# torque.net
KiCad netlist of a schematic drawn in EAGLE
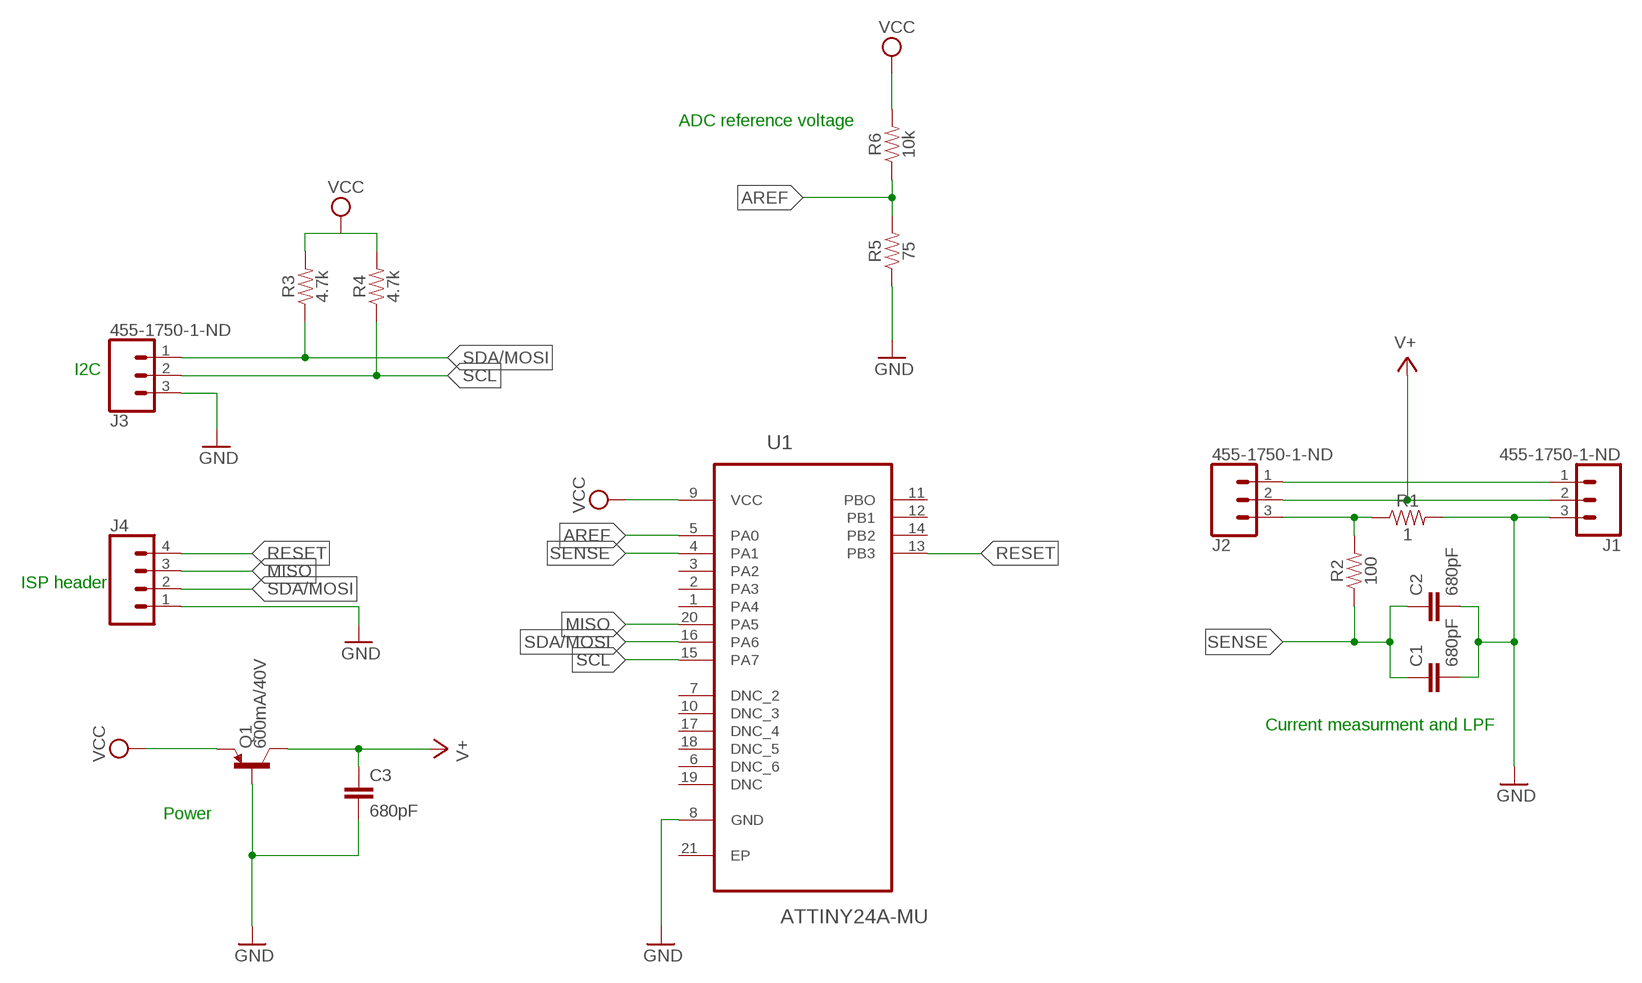
[diagram p0: schematic, sheet 1]

(export (version "E")
  (design (tool "Eeschema 10.0.6"))
  (components
    (comp (ref "C1")
      (value "680pF")
      (footprint "eagle-import:0603")
      (libsource (lib "eagle-import") (part "680PF-0603-50V-10%"))
    )
    (comp (ref "C2")
      (value "680pF")
      (footprint "eagle-import:0603")
      (libsource (lib "eagle-import") (part "680PF-0603-50V-10%"))
    )
    (comp (ref "C3")
      (value "680pF")
      (footprint "eagle-import:0603")
      (libsource (lib "eagle-import") (part "680PF-0603-50V-10%"))
    )
    (comp (ref "J1")
      (value "455-1750-1-ND")
      (footprint "eagle-import:1X03")
      (libsource (lib "eagle-import") (part "CONN_03"))
    )
    (comp (ref "J2")
      (value "455-1750-1-ND")
      (footprint "eagle-import:1X03")
      (libsource (lib "eagle-import") (part "CONN_03"))
    )
    (comp (ref "J3")
      (value "455-1750-1-ND")
      (footprint "eagle-import:1X03")
      (libsource (lib "eagle-import") (part "CONN_03"))
    )
    (comp (ref "J4")
      (value "CONN_04SMD_RA_FEMALE")
      (footprint "eagle-import:1X04_SMD_RA_FEMALE")
      (libsource (lib "eagle-import") (part "CONN_04SMD_RA_FEMALE"))
    )
    (comp (ref "Q1")
      (value "600mA/40V")
      (footprint "eagle-import:SOT23-3")
      (libsource (lib "eagle-import") (part "TRANS_PNP-MMBT4403"))
    )
    (comp (ref "R1")
      (value "1")
      (footprint "eagle-import:0603")
      (libsource (lib "eagle-import") (part "1OHM-0603-1/10W-1%"))
    )
    (comp (ref "R2")
      (value "100")
      (footprint "eagle-import:0603")
      (libsource (lib "eagle-import") (part "100OHM-0603-1/10W-1%"))
    )
    (comp (ref "R3")
      (value "4.7k")
      (footprint "eagle-import:0603")
      (libsource (lib "eagle-import") (part "4.7KOHM-0603-1/10W-1%"))
    )
    (comp (ref "R4")
      (value "4.7k")
      (footprint "eagle-import:0603")
      (libsource (lib "eagle-import") (part "4.7KOHM-0603-1/10W-1%"))
    )
    (comp (ref "R5")
      (value "75")
      (footprint "eagle-import:0603")
      (libsource (lib "eagle-import") (part "75KOHM-0603-1/10W-1%"))
    )
    (comp (ref "R6")
      (value "10k")
      (footprint "eagle-import:0603")
      (libsource (lib "eagle-import") (part "10KOHM-0603-1/10W-1%"))
    )
    (comp (ref "U1")
      (value "ATTINY24A-MU")
      (footprint "eagle-import:QFN50P400X400X80-21N")
      (libsource (lib "eagle-import") (part "ATTINY24A-MU"))
    )
  )
  (nets
    (net (code "1") (name "AREF") (class "Default")
      (node (ref "R5") (pin "2") (pinfunction "2_2") (pintype "passive"))
      (node (ref "R6") (pin "1") (pinfunction "1_1") (pintype "passive"))
      (node (ref "U1") (pin "5") (pinfunction "PA0_5") (pintype "bidirectional"))
    )
    (net (code "2") (name "GND") (class "Default")
      (node (ref "C1") (pin "2") (pinfunction "2_2") (pintype "passive"))
      (node (ref "C2") (pin "2") (pinfunction "2_2") (pintype "passive"))
      (node (ref "C3") (pin "2") (pinfunction "2_2") (pintype "passive"))
      (node (ref "J1") (pin "3") (pinfunction "3_3") (pintype "passive"))
      (node (ref "J3") (pin "3") (pinfunction "3_3") (pintype "passive"))
      (node (ref "J4") (pin "1") (pinfunction "1_1") (pintype "passive"))
      (node (ref "Q1") (pin "1") (pinfunction "B_1") (pintype "passive"))
      (node (ref "R1") (pin "2") (pinfunction "2_2") (pintype "passive"))
      (node (ref "R5") (pin "1") (pinfunction "1_1") (pintype "passive"))
      (node (ref "U1") (pin "8") (pinfunction "GND_8") (pintype "passive"))
    )
    (net (code "3") (name "MISO") (class "Default")
      (node (ref "J4") (pin "3") (pinfunction "3_3") (pintype "passive"))
      (node (ref "U1") (pin "20") (pinfunction "PA5_20") (pintype "bidirectional"))
    )
    (net (code "4") (name "Net-(J1-Pad1)") (class "Default")
      (node (ref "J1") (pin "1") (pinfunction "1_1") (pintype "passive"))
      (node (ref "J2") (pin "1") (pinfunction "1_1") (pintype "passive"))
    )
    (net (code "5") (name "Net-(J2-Pad3)") (class "Default")
      (node (ref "J2") (pin "3") (pinfunction "3_3") (pintype "passive"))
      (node (ref "R1") (pin "1") (pinfunction "1_1") (pintype "passive"))
      (node (ref "R2") (pin "2") (pinfunction "2_2") (pintype "passive"))
    )
    (net (code "6") (name "Net-(R3-Pad2)") (class "Default")
      (node (ref "R3") (pin "2") (pinfunction "2_2") (pintype "passive"))
      (node (ref "R4") (pin "2") (pinfunction "2_2") (pintype "passive"))
    )
    (net (code "7") (name "RESET") (class "Default")
      (node (ref "J4") (pin "4") (pinfunction "4_4") (pintype "passive"))
      (node (ref "U1") (pin "13") (pinfunction "PB3_13") (pintype "bidirectional"))
    )
    (net (code "8") (name "SCL") (class "Default")
      (node (ref "J3") (pin "2") (pinfunction "2_2") (pintype "passive"))
      (node (ref "R4") (pin "1") (pinfunction "1_1") (pintype "passive"))
      (node (ref "U1") (pin "15") (pinfunction "PA7_15") (pintype "bidirectional"))
    )
    (net (code "9") (name "SDA{slash}MOSI") (class "Default")
      (node (ref "J3") (pin "1") (pinfunction "1_1") (pintype "passive"))
      (node (ref "J4") (pin "2") (pinfunction "2_2") (pintype "passive"))
      (node (ref "R3") (pin "1") (pinfunction "1_1") (pintype "passive"))
      (node (ref "U1") (pin "16") (pinfunction "PA6_16") (pintype "bidirectional"))
    )
    (net (code "10") (name "SENSE") (class "Default")
      (node (ref "C1") (pin "1") (pinfunction "1_1") (pintype "passive"))
      (node (ref "C2") (pin "1") (pinfunction "1_1") (pintype "passive"))
      (node (ref "R2") (pin "1") (pinfunction "1_1") (pintype "passive"))
      (node (ref "U1") (pin "4") (pinfunction "PA1_4") (pintype "bidirectional"))
    )
    (net (code "11") (name "V+") (class "Default")
      (node (ref "C3") (pin "1") (pinfunction "1_1") (pintype "passive"))
      (node (ref "J1") (pin "2") (pinfunction "2_2") (pintype "passive"))
      (node (ref "J2") (pin "2") (pinfunction "2_2") (pintype "passive"))
      (node (ref "Q1") (pin "3") (pinfunction "C_3") (pintype "passive"))
    )
    (net (code "12") (name "VCC") (class "Default")
      (node (ref "Q1") (pin "2") (pinfunction "E_2") (pintype "passive"))
      (node (ref "R6") (pin "2") (pinfunction "2_2") (pintype "passive"))
      (node (ref "U1") (pin "9") (pinfunction "VCC_9") (pintype "power_in"))
    )
    (net (code "13") (name "unconnected-(U1-DNC-Pad19)") (class "Default")
      (node (ref "U1") (pin "19") (pinfunction "DNC_19") (pintype "no_connect"))
    )
    (net (code "14") (name "unconnected-(U1-DNC_2-Pad7)") (class "Default")
      (node (ref "U1") (pin "7") (pinfunction "DNC_2_7") (pintype "no_connect"))
    )
    (net (code "15") (name "unconnected-(U1-DNC_3-Pad10)") (class "Default")
      (node (ref "U1") (pin "10") (pinfunction "DNC_3_10") (pintype "no_connect"))
    )
    (net (code "16") (name "unconnected-(U1-DNC_4-Pad17)") (class "Default")
      (node (ref "U1") (pin "17") (pinfunction "DNC_4_17") (pintype "no_connect"))
    )
    (net (code "17") (name "unconnected-(U1-DNC_5-Pad18)") (class "Default")
      (node (ref "U1") (pin "18") (pinfunction "DNC_5_18") (pintype "no_connect"))
    )
    (net (code "18") (name "unconnected-(U1-DNC_6-Pad6)") (class "Default")
      (node (ref "U1") (pin "6") (pinfunction "DNC_6_6") (pintype "no_connect"))
    )
    (net (code "19") (name "unconnected-(U1-EP-Pad21)") (class "Default")
      (node (ref "U1") (pin "21") (pinfunction "EP_21") (pintype "passive"))
    )
    (net (code "20") (name "unconnected-(U1-PA2-Pad3)") (class "Default")
      (node (ref "U1") (pin "3") (pinfunction "PA2_3") (pintype "bidirectional"))
    )
    (net (code "21") (name "unconnected-(U1-PA3-Pad2)") (class "Default")
      (node (ref "U1") (pin "2") (pinfunction "PA3_2") (pintype "bidirectional"))
    )
    (net (code "22") (name "unconnected-(U1-PA4-Pad1)") (class "Default")
      (node (ref "U1") (pin "1") (pinfunction "PA4_1") (pintype "bidirectional"))
    )
    (net (code "23") (name "unconnected-(U1-PB1-Pad12)") (class "Default")
      (node (ref "U1") (pin "12") (pinfunction "PB1_12") (pintype "bidirectional"))
    )
    (net (code "24") (name "unconnected-(U1-PB2-Pad14)") (class "Default")
      (node (ref "U1") (pin "14") (pinfunction "PB2_14") (pintype "bidirectional"))
    )
    (net (code "25") (name "unconnected-(U1-PBO-Pad11)") (class "Default")
      (node (ref "U1") (pin "11") (pinfunction "PBO_11") (pintype "bidirectional"))
    )
  )
)
